# isp_2.net
KiCad netlist of a schematic drawn in EAGLE
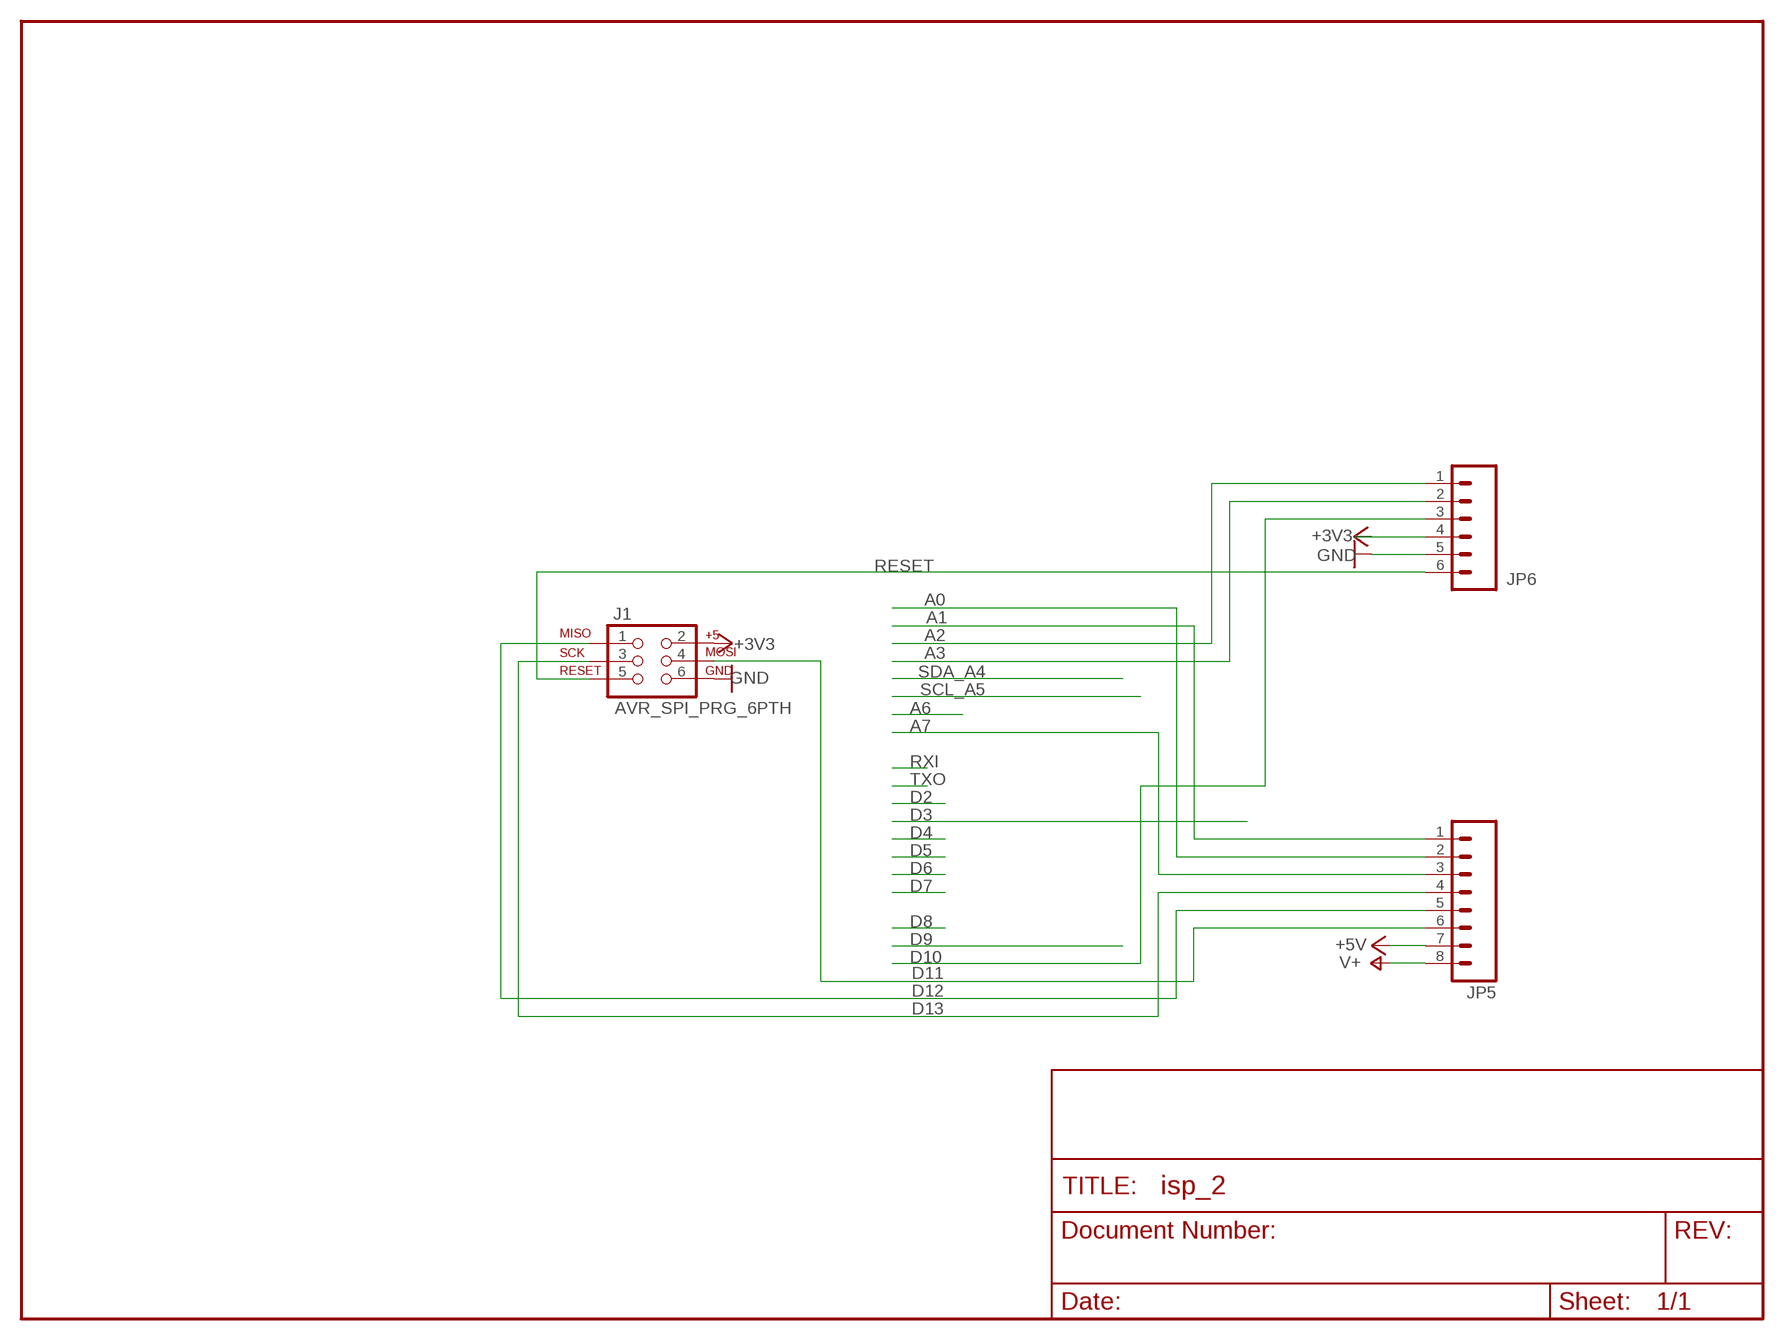
[diagram p0: schematic, sheet 1]

(export (version "E")
  (design (tool "Eeschema 10.0.6"))
  (components
    (comp (ref "J1")
      (value "AVR_SPI_PRG_6PTH")
      (footprint "eagle-import:2X3")
      (libsource (lib "eagle-import") (part "AVR_SPI_PRG_6PTH"))
    )
    (comp (ref "JP5")
      (value "M081X08")
      (footprint "eagle-import:1X08")
      (libsource (lib "eagle-import") (part "M081X08"))
    )
    (comp (ref "JP6")
      (value "M06SIP")
      (footprint "eagle-import:1X06")
      (libsource (lib "eagle-import") (part "M06SIP"))
    )
  )
  (nets
    (net (code "1") (name "+3V3") (class "Default")
      (node (ref "J1") (pin "2") (pinfunction "2_2") (pintype "passive"))
      (node (ref "JP6") (pin "4") (pinfunction "4_4") (pintype "passive"))
    )
    (net (code "2") (name "+5V") (class "Default")
      (node (ref "JP5") (pin "7") (pinfunction "7_7") (pintype "passive"))
    )
    (net (code "3") (name "/A0") (class "Default")
      (node (ref "JP5") (pin "2") (pinfunction "2_2") (pintype "passive"))
    )
    (net (code "4") (name "/A1") (class "Default")
      (node (ref "JP5") (pin "1") (pinfunction "1_1") (pintype "passive"))
    )
    (net (code "5") (name "/A2") (class "Default")
      (node (ref "JP6") (pin "1") (pinfunction "1_1") (pintype "passive"))
    )
    (net (code "6") (name "/A3") (class "Default")
      (node (ref "JP6") (pin "2") (pinfunction "2_2") (pintype "passive"))
    )
    (net (code "8") (name "/A7") (class "Default")
      (node (ref "JP5") (pin "3") (pinfunction "3_3") (pintype "passive"))
    )
    (net (code "17") (name "/D10") (class "Default")
      (node (ref "JP6") (pin "3") (pinfunction "3_3") (pintype "passive"))
    )
    (net (code "18") (name "/D11") (class "Default")
      (node (ref "J1") (pin "4") (pinfunction "4_4") (pintype "passive"))
      (node (ref "JP5") (pin "6") (pinfunction "6_6") (pintype "passive"))
    )
    (net (code "19") (name "/D12") (class "Default")
      (node (ref "J1") (pin "1") (pinfunction "1_1") (pintype "passive"))
      (node (ref "JP5") (pin "5") (pinfunction "5_5") (pintype "passive"))
    )
    (net (code "20") (name "/D13") (class "Default")
      (node (ref "J1") (pin "3") (pinfunction "3_3") (pintype "passive"))
      (node (ref "JP5") (pin "4") (pinfunction "4_4") (pintype "passive"))
    )
    (net (code "21") (name "/RESET") (class "Default")
      (node (ref "J1") (pin "5") (pinfunction "5_5") (pintype "passive"))
      (node (ref "JP6") (pin "6") (pinfunction "6_6") (pintype "passive"))
    )
    (net (code "26") (name "GND") (class "Default")
      (node (ref "J1") (pin "6") (pinfunction "6_6") (pintype "passive"))
      (node (ref "JP6") (pin "5") (pinfunction "5_5") (pintype "passive"))
    )
    (net (code "27") (name "V+") (class "Default")
      (node (ref "JP5") (pin "8") (pinfunction "8_8") (pintype "passive"))
    )
  )
)
